# AudioUFO.net
KiCad netlist of a schematic drawn in Altium Designer
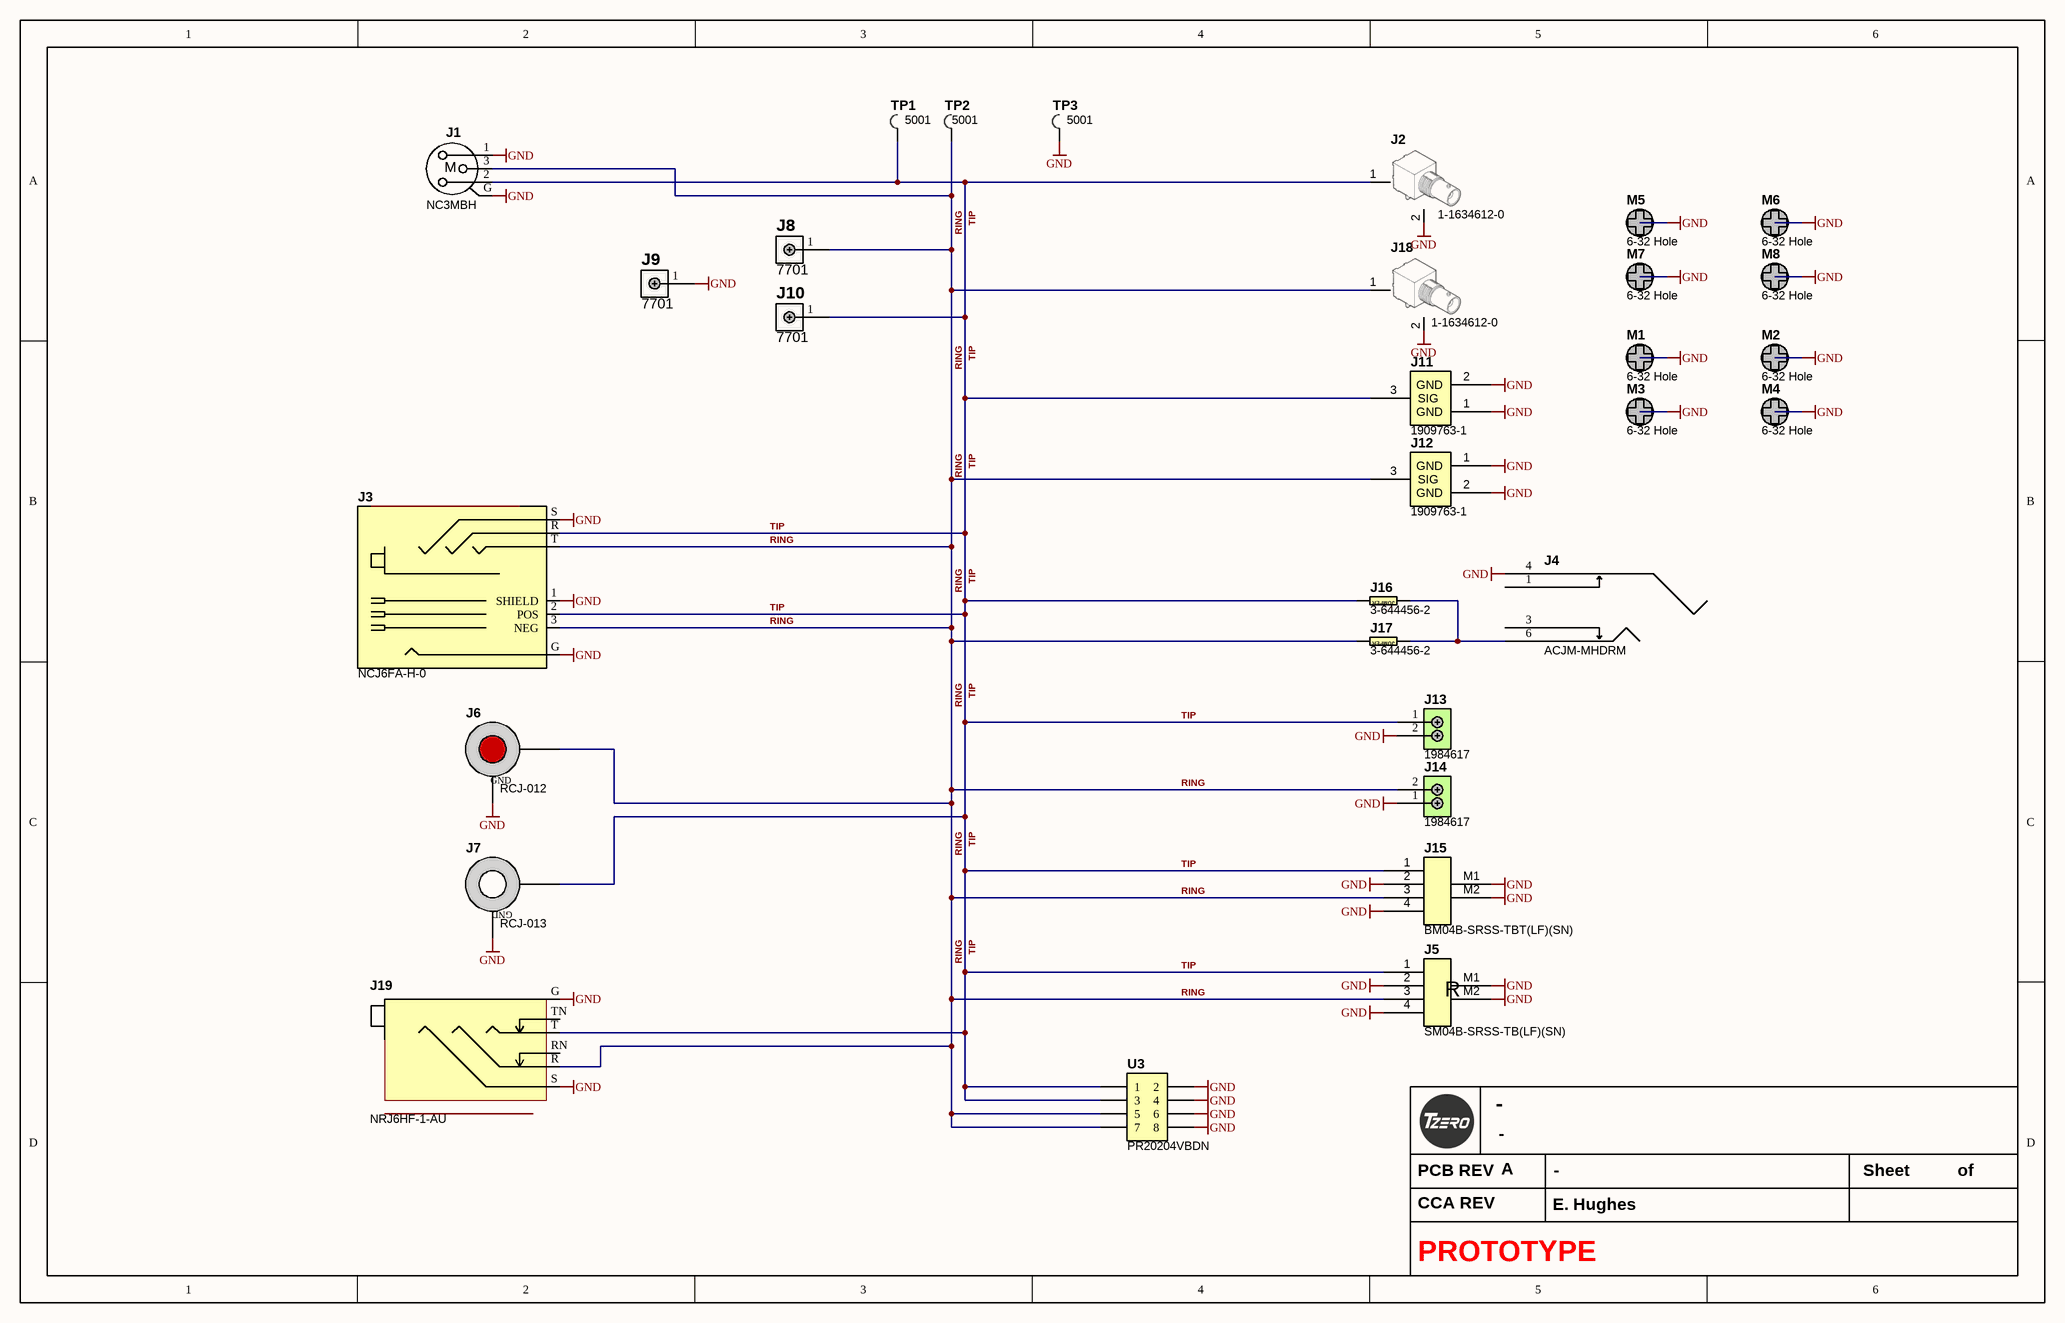
[diagram p0: AudioUFO.SchDoc]

(export (version "E")
  (design (tool "Eeschema 10.0.6"))
  (components
    (comp (ref "J1")
      (value "NC3MBH")
      (footprint "NC3MBH")
      (description "XLR 3-Pin Male Right Angle")
      (fields (field (name "MF") "NEUTRIK") (field (name "MANUFACTURER PART NUMBER") "NC3MBH-1"))
      (libsource (lib "eConnector") (part "NC3MBH"))
    )
    (comp (ref "J2")
      (value "1-1634612-0")
      (footprint "1-1634612-0")
      (fields (field (name "MANUFACTURER") "TE Connectivity"))
      (libsource (lib "eConnector_RF") (part "1-1634612-0"))
    )
    (comp (ref "J3")
      (value "NCJ6FA-H-0")
      (footprint "NEUTRIK_NCJ6FA-H-0")
      (description "XLR Connectors A SERIES COMBO;3POLE FEM;NOLATCH;RET SPRG")
      (fields (field (name "MANUFACTURER") "Neutrik") (field (name "VOLTAGE") "50 V"))
      (libsource (lib "eConnector_Audio") (part "NCJ6FA-H-0"))
    )
    (comp (ref "J4")
      (value "ACJM-MHDRM")
      (footprint "ACJS-MHDR")
      (description "Phone Connectors 1/4\"HOR Snap-fit CHASSIS CONN")
      (fields (field (name "MANUFACTURER") "Amphenol Audio"))
      (libsource (lib "eConnector_Audio") (part "ACJM-MHDRM"))
    )
    (comp (ref "J5")
      (value "SM04B-SRSS-TB(LF)(SN)")
      (footprint "SM04B-SRSS-TB(LF)(SN)")
      (description "Conn Shrouded Header HDR 4 POS 1mm Solder RA SMD T/R")
      (fields (field (name "MANUFACTURER") "JST"))
      (libsource (lib "eConnector_JST_SM") (part "SM04B-SRSS-TB(LF)(SN)"))
    )
    (comp (ref "J6")
      (value "RCJ-012")
      (footprint "RCJ-014")
      (description "CONN RCA JACK METAL R/A YEL PCB")
      (fields (field (name "MANUFACTURER") "CUI Inc"))
      (libsource (lib "eConnector_Audio") (part "RCJ-012"))
    )
    (comp (ref "J7")
      (value "RCJ-013")
      (footprint "RCJ-014")
      (description "CONN RCA JACK METAL R/A WHITE PCB")
      (fields (field (name "MANUFACTURER") "CUI Inc"))
      (libsource (lib "eConnector_Audio") (part "RCJ-013"))
    )
    (comp (ref "J8")
      (value "7701")
      (footprint "7701")
      (description "TERM W/ASSEMBLD SCREW VERT PCMNT")
      (fields (field (name "MANUFACTURER") "Keystone Electronics"))
      (libsource (lib "eConnector") (part "7701"))
    )
    (comp (ref "J9")
      (value "7701")
      (footprint "7701")
      (description "TERM W/ASSEMBLD SCREW VERT PCMNT")
      (fields (field (name "MANUFACTURER") "Keystone Electronics"))
      (libsource (lib "eConnector") (part "7701"))
    )
    (comp (ref "J10")
      (value "7701")
      (footprint "7701")
      (description "TERM W/ASSEMBLD SCREW VERT PCMNT")
      (fields (field (name "MANUFACTURER") "Keystone Electronics"))
      (libsource (lib "eConnector") (part "7701"))
    )
    (comp (ref "J11")
      (value "1909763-1")
      (footprint "1909763-1")
      (description "CONN UMCC JACK STR 50OHM SMD")
      (fields (field (name "MANUFACTURER") "TE Connectivity AMP Connectors"))
      (libsource (lib "") (part "1909763-1_1"))
    )
    (comp (ref "J12")
      (value "1909763-1")
      (footprint "1909763-1")
      (description "CONN UMCC JACK STR 50OHM SMD")
      (fields (field (name "MANUFACTURER") "TE Connectivity AMP Connectors"))
      (libsource (lib "eConnector_RF") (part "1909763-1"))
    )
    (comp (ref "J13")
      (value "1984617")
      (footprint "1984617")
      (description "CONN TERM BLOCK T/H 2POS 3.5MM")
      (fields (field (name "MANUFACTURER") "Phoenix Contact") (field (name "VOLTAGE") "300V"))
      (libsource (lib "eConnector_TerminalBlock") (part "1984617"))
    )
    (comp (ref "J14")
      (value "1984617")
      (footprint "1984617")
      (description "CONN TERM BLOCK T/H 2POS 3.5MM")
      (fields (field (name "MANUFACTURER") "Phoenix Contact") (field (name "VOLTAGE") "300V"))
      (libsource (lib "") (part "1984617_1"))
    )
    (comp (ref "J15")
      (value "BM04B-SRSS-TBT(LF)(SN)")
      (footprint "BM04B-SRSS-TBT(LF)(SN)")
      (description "1.0mm Pitch, Ultra-Compact, Low Profile Design, Interchangeable Shrouded Header")
      (fields (field (name "MANUFACTURER") "JST"))
      (libsource (lib "eConnector_JST_SM") (part "BM04B-SRSS-TBT(LF)(SN)"))
    )
    (comp (ref "J16")
      (value "3-644456-2")
      (footprint "3-644456-2")
      (description "CONN HEADER VERT 2POS .100 TIN")
      (fields (field (name "MANUFACTURER") "TE Connectivity"))
      (libsource (lib "eConnector") (part "3-644456-2"))
    )
    (comp (ref "J17")
      (value "3-644456-2")
      (footprint "3-644456-2")
      (description "CONN HEADER VERT 2POS .100 TIN")
      (fields (field (name "MANUFACTURER") "TE Connectivity"))
      (libsource (lib "eConnector") (part "3-644456-2"))
    )
    (comp (ref "J18")
      (value "1-1634612-0")
      (footprint "1-1634612-0")
      (fields (field (name "MANUFACTURER") "TE Connectivity"))
      (libsource (lib "eConnector_RF") (part "1-1634612-0"))
    )
    (comp (ref "J19")
      (value "NRJ6HF-1-AU")
      (footprint "NEUTRIK_NRJ6HF-1")
      (description "Phone Connectors 1/4\" JACK STEREO SW SLIM-FULL THREAD NSE")
      (fields (field (name "MANUFACTURER") "Neutrik"))
      (libsource (lib "eConnector_Audio") (part "NRJ6HF-1-AU"))
    )
    (comp (ref "M1")
      (value "6-32 Hole")
      (footprint "6-32 X 0")
      (fields (field (name "SOURCE") "Digikey"))
      (libsource (lib "EMechanical") (part "6-32 Hole"))
    )
    (comp (ref "M2")
      (value "6-32 Hole")
      (footprint "6-32 X 0")
      (fields (field (name "SOURCE") "Digikey"))
      (libsource (lib "EMechanical") (part "6-32 Hole"))
    )
    (comp (ref "M3")
      (value "6-32 Hole")
      (footprint "6-32 X 0")
      (fields (field (name "SOURCE") "Digikey"))
      (libsource (lib "EMechanical") (part "6-32 Hole"))
    )
    (comp (ref "M4")
      (value "6-32 Hole")
      (footprint "6-32 X 0")
      (fields (field (name "SOURCE") "Digikey"))
      (libsource (lib "EMechanical") (part "6-32 Hole"))
    )
    (comp (ref "M5")
      (value "6-32 Hole")
      (footprint "6-32 X 0")
      (fields (field (name "SOURCE") "Digikey"))
      (libsource (lib "EMechanical") (part "6-32 Hole"))
    )
    (comp (ref "M6")
      (value "6-32 Hole")
      (footprint "6-32 X 0")
      (fields (field (name "SOURCE") "Digikey"))
      (libsource (lib "EMechanical") (part "6-32 Hole"))
    )
    (comp (ref "M7")
      (value "6-32 Hole")
      (footprint "6-32 X 0")
      (fields (field (name "SOURCE") "Digikey"))
      (libsource (lib "EMechanical") (part "6-32 Hole"))
    )
    (comp (ref "M8")
      (value "6-32 Hole")
      (footprint "6-32 X 0")
      (fields (field (name "SOURCE") "Digikey"))
      (libsource (lib "EMechanical") (part "6-32 Hole"))
    )
    (comp (ref "TP1")
      (value "5001")
      (footprint "5001")
      (description "KEYSTONE - 5001 - TEST POINT, CONNECTOR, BLACK")
      (fields (field (name "MANUFACTURER") "Keystone Electronics"))
      (libsource (lib "eTestPoint") (part "5001"))
    )
    (comp (ref "TP2")
      (value "5001")
      (footprint "5001")
      (description "KEYSTONE - 5001 - TEST POINT, CONNECTOR, BLACK")
      (fields (field (name "MANUFACTURER") "Keystone Electronics"))
      (libsource (lib "eTestPoint") (part "5001"))
    )
    (comp (ref "TP3")
      (value "5001")
      (footprint "5001")
      (description "KEYSTONE - 5001 - TEST POINT, CONNECTOR, BLACK")
      (fields (field (name "MANUFACTURER") "Keystone Electronics"))
      (libsource (lib "eTestPoint") (part "5001"))
    )
    (comp (ref "U3")
      (value "PR20204VBDN")
      (footprint "HEADER 2x4 .100\"")
      (description "2x4 Header .100\"")
      (fields (field (name "MANUFACTURER") "METZ CONNECT"))
      (libsource (lib "eConnector_Header") (part "PR20204VBDN"))
    )
  )
  (nets
    (net (code "1") (name "/RING") (class "Default")
      (node (ref "J1") (pin "3") (pinfunction "3_3") (pintype "passive"))
      (node (ref "J12") (pin "3") (pinfunction "SIG_3") (pintype "passive"))
      (node (ref "J14") (pin "2") (pinfunction "2_2") (pintype "passive"))
      (node (ref "J15") (pin "3") (pinfunction "3_3") (pintype "passive"))
      (node (ref "J17") (pin "2") (pinfunction "2_2") (pintype "passive"))
      (node (ref "J18") (pin "1") (pinfunction "1_1") (pintype "passive"))
      (node (ref "J19") (pin "R") (pinfunction "R_R") (pintype "passive"))
      (node (ref "J3") (pin "3") (pinfunction "NEG_3") (pintype "passive"))
      (node (ref "J3") (pin "T") (pinfunction "T_T") (pintype "passive"))
      (node (ref "J5") (pin "3") (pinfunction "3_3") (pintype "passive"))
      (node (ref "J6") (pin "2") (pinfunction "Signal_2") (pintype "passive"))
      (node (ref "J8") (pin "1") (pinfunction "1_1") (pintype "passive"))
      (node (ref "TP2") (pin "1") (pinfunction "1_1") (pintype "passive"))
      (node (ref "U3") (pin "5") (pinfunction "5_5") (pintype "passive"))
      (node (ref "U3") (pin "7") (pinfunction "7_7") (pintype "passive"))
    )
    (net (code "2") (name "/TIP") (class "Default")
      (node (ref "J1") (pin "2") (pinfunction "2_2") (pintype "passive"))
      (node (ref "J10") (pin "1") (pinfunction "1_1") (pintype "passive"))
      (node (ref "J11") (pin "3") (pinfunction "SIG_3") (pintype "passive"))
      (node (ref "J13") (pin "1") (pinfunction "1_1") (pintype "passive"))
      (node (ref "J15") (pin "1") (pinfunction "1_1") (pintype "passive"))
      (node (ref "J16") (pin "2") (pinfunction "2_2") (pintype "passive"))
      (node (ref "J19") (pin "T") (pinfunction "T_T") (pintype "passive"))
      (node (ref "J2") (pin "1") (pinfunction "1_1") (pintype "passive"))
      (node (ref "J3") (pin "2") (pinfunction "POS_2") (pintype "passive"))
      (node (ref "J3") (pin "R") (pinfunction "R_R") (pintype "passive"))
      (node (ref "J5") (pin "1") (pinfunction "1_1") (pintype "passive"))
      (node (ref "J7") (pin "2") (pinfunction "Signal_2") (pintype "passive"))
      (node (ref "TP1") (pin "1") (pinfunction "1_1") (pintype "passive"))
      (node (ref "U3") (pin "1") (pinfunction "1_1") (pintype "passive"))
      (node (ref "U3") (pin "3") (pinfunction "3_3") (pintype "passive"))
    )
    (net (code "3") (name "GND") (class "Default")
      (node (ref "J1") (pin "1") (pinfunction "1_1") (pintype "passive"))
      (node (ref "J1") (pin "G") (pinfunction "G_G") (pintype "passive"))
      (node (ref "J11") (pin "1") (pinfunction "GND_1") (pintype "passive"))
      (node (ref "J11") (pin "2") (pinfunction "GND_2") (pintype "passive"))
      (node (ref "J12") (pin "1") (pinfunction "GND_1") (pintype "passive"))
      (node (ref "J12") (pin "2") (pinfunction "GND_2") (pintype "passive"))
      (node (ref "J13") (pin "2") (pinfunction "2_2") (pintype "passive"))
      (node (ref "J14") (pin "1") (pinfunction "1_1") (pintype "passive"))
      (node (ref "J15") (pin "2") (pinfunction "2_2") (pintype "passive"))
      (node (ref "J15") (pin "4") (pinfunction "4_4") (pintype "passive"))
      (node (ref "J15") (pin "M1") (pinfunction "M1_M1") (pintype "passive"))
      (node (ref "J15") (pin "M2") (pinfunction "M2_M2") (pintype "passive"))
      (node (ref "J18") (pin "2") (pinfunction "2_2") (pintype "passive"))
      (node (ref "J19") (pin "G") (pinfunction "G_G") (pintype "passive"))
      (node (ref "J19") (pin "S") (pinfunction "S_S") (pintype "passive"))
      (node (ref "J2") (pin "2") (pinfunction "2_2") (pintype "passive"))
      (node (ref "J3") (pin "1") (pinfunction "SHIELD_1") (pintype "passive"))
      (node (ref "J3") (pin "G") (pinfunction "G_G") (pintype "passive"))
      (node (ref "J3") (pin "S") (pinfunction "S_S") (pintype "passive"))
      (node (ref "J4") (pin "4") (pinfunction "4_4") (pintype "passive"))
      (node (ref "J5") (pin "2") (pinfunction "2_2") (pintype "passive"))
      (node (ref "J5") (pin "4") (pinfunction "4_4") (pintype "passive"))
      (node (ref "J5") (pin "M1") (pinfunction "M1_M1") (pintype "passive"))
      (node (ref "J5") (pin "M2") (pinfunction "M2_M2") (pintype "passive"))
      (node (ref "J6") (pin "1") (pinfunction "1_1") (pintype "passive"))
      (node (ref "J7") (pin "1") (pinfunction "1_1") (pintype "passive"))
      (node (ref "J9") (pin "1") (pinfunction "1_1") (pintype "passive"))
      (node (ref "M1") (pin "1") (pinfunction "1_1") (pintype "passive"))
      (node (ref "M2") (pin "1") (pinfunction "1_1") (pintype "passive"))
      (node (ref "M3") (pin "1") (pinfunction "1_1") (pintype "passive"))
      (node (ref "M4") (pin "1") (pinfunction "1_1") (pintype "passive"))
      (node (ref "M5") (pin "1") (pinfunction "1_1") (pintype "passive"))
      (node (ref "M6") (pin "1") (pinfunction "1_1") (pintype "passive"))
      (node (ref "M7") (pin "1") (pinfunction "1_1") (pintype "passive"))
      (node (ref "M8") (pin "1") (pinfunction "1_1") (pintype "passive"))
      (node (ref "TP3") (pin "1") (pinfunction "1_1") (pintype "passive"))
      (node (ref "U3") (pin "2") (pinfunction "2_2") (pintype "passive"))
      (node (ref "U3") (pin "4") (pinfunction "4_4") (pintype "passive"))
      (node (ref "U3") (pin "6") (pinfunction "6_6") (pintype "passive"))
      (node (ref "U3") (pin "8") (pinfunction "8_8") (pintype "passive"))
    )
    (net (code "4") (name "Net-(J16-Pad1)") (class "Default")
      (node (ref "J16") (pin "1") (pinfunction "1_1") (pintype "passive"))
      (node (ref "J17") (pin "1") (pinfunction "1_1") (pintype "passive"))
      (node (ref "J4") (pin "6") (pinfunction "6_6") (pintype "passive"))
    )
    (net (code "5") (name "unconnected-(J4-Pad1)") (class "Default")
      (node (ref "J4") (pin "1") (pinfunction "1_1") (pintype "passive"))
    )
    (net (code "6") (name "unconnected-(J4-Pad3)") (class "Default")
      (node (ref "J4") (pin "3") (pinfunction "3_3") (pintype "passive"))
    )
    (net (code "7") (name "unconnected-(J19-PadRN)") (class "Default")
      (node (ref "J19") (pin "RN") (pinfunction "RN_RN") (pintype "passive"))
    )
    (net (code "8") (name "unconnected-(J19-PadTN)") (class "Default")
      (node (ref "J19") (pin "TN") (pinfunction "TN_TN") (pintype "passive"))
    )
  )
)
